# 5_-MCU_POWER.net
KiCad netlist of a schematic drawn in Altium Designer
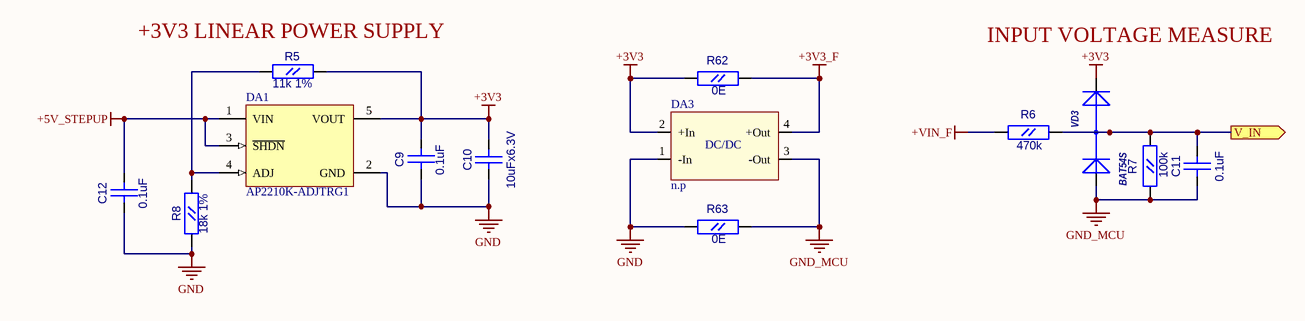
[diagram p0: [5]-MCU_POWER.SchDoc]

(export (version "E")
  (design (tool "Eeschema 10.0.6"))
  (components
    (comp (ref "C9")
      (value "0.1uF")
      (footprint "CC0603")
      (description "CC0603")
      (libsource (lib "gprs_modem_2") (part "CC0603"))
    )
    (comp (ref "C10")
      (value "10uFx6.3V")
      (footprint "CC0805")
      (description "CC0805")
      (libsource (lib "gprs_modem_2") (part "CC0805"))
    )
    (comp (ref "C11")
      (value "0.1uF")
      (footprint "CC0603")
      (description "CC0603")
      (libsource (lib "gprs_modem_2") (part "CC0603"))
    )
    (comp (ref "C12")
      (value "0.1uF")
      (footprint "CC0603")
      (description "CC0603")
      (libsource (lib "gprs_modem_2") (part "CC0603"))
    )
    (comp (ref "DA1")
      (value "AP2210K-ADJTRG1")
      (footprint "SOT23-5")
      (fields (field (name "PUBLISHER") "Altium Limited"))
      (libsource (lib "gprs_modem_2") (part "MCP1824T-ADJE/OT"))
    )
    (comp (ref "DA3")
      (value "n.p")
      (footprint "CME0303S3C")
      (description "DC/DC converter")
      (libsource (lib "fizik_lib") (part "CME0303S3C"))
    )
    (comp (ref "R5")
      (value "11k 1%")
      (footprint "RC0603")
      (description "RC0603")
      (libsource (lib "gprs_modem_2") (part "RC0603"))
    )
    (comp (ref "R6")
      (value "470k")
      (footprint "RC0603")
      (description "RC0603")
      (libsource (lib "fizik_lib") (part "RC0603"))
    )
    (comp (ref "R7")
      (value "100k")
      (footprint "RC0603")
      (description "RC0603")
      (libsource (lib "gprs_modem_2") (part "RC0603"))
    )
    (comp (ref "R8")
      (value "18k 1%")
      (footprint "RC0603")
      (description "RC0603")
      (libsource (lib "gprs_modem_2") (part "RC0603"))
    )
    (comp (ref "R62")
      (value "0E")
      (footprint "RC0805")
      (description "RC0805")
      (libsource (lib "fizik_lib") (part "RC0805"))
    )
    (comp (ref "R63")
      (value "0E")
      (footprint "RC0805")
      (description "RC0805")
      (libsource (lib "fizik_lib") (part "RC0805"))
    )
    (comp (ref "VD3")
      (value "BAT54S")
      (footprint "SOT-23(GSD)")
      (description "1.0 Ampere General Purpose Rectifier")
      (libsource (lib "gprs_modem_2") (part "BAT54S"))
    )
  )
  (nets
    (net (code "1") (name "+3V3") (class "Default")
      (node (ref "C10") (pin "2") (pinfunction "B_2") (pintype "passive"))
      (node (ref "C9") (pin "1") (pinfunction "A_1") (pintype "passive"))
      (node (ref "DA1") (pin "5") (pinfunction "VOUT_5") (pintype "power_in"))
      (node (ref "DA3") (pin "2") (pinfunction "+In_2") (pintype "passive"))
      (node (ref "R5") (pin "2") (pinfunction "B_2") (pintype "passive"))
      (node (ref "R62") (pin "1") (pinfunction "A_1") (pintype "passive"))
      (node (ref "VD3") (pin "2") (pinfunction "K_2") (pintype "passive"))
    )
    (net (code "2") (name "+3V3_F") (class "Default")
      (node (ref "DA3") (pin "4") (pinfunction "+Out_4") (pintype "passive"))
      (node (ref "R62") (pin "2") (pinfunction "B_2") (pintype "passive"))
    )
    (net (code "3") (name "+5V_STEPUP") (class "Default")
      (node (ref "C12") (pin "1") (pinfunction "A_1") (pintype "passive"))
      (node (ref "DA1") (pin "1") (pinfunction "VIN_1") (pintype "power_in"))
      (node (ref "DA1") (pin "3") (pinfunction "~{SHDN}_3") (pintype "input"))
    )
    (net (code "4") (name "+VIN_F") (class "Default")
      (node (ref "R6") (pin "1") (pinfunction "A_1") (pintype "passive"))
    )
    (net (code "5") (name "/V_IN") (class "Default")
      (node (ref "C11") (pin "2") (pinfunction "B_2") (pintype "passive"))
      (node (ref "R6") (pin "2") (pinfunction "B_2") (pintype "passive"))
      (node (ref "R7") (pin "2") (pinfunction "B_2") (pintype "passive"))
      (node (ref "VD3") (pin "3") (pinfunction "AK_3") (pintype "passive"))
    )
    (net (code "6") (name "GND") (class "Default")
      (node (ref "C10") (pin "1") (pinfunction "A_1") (pintype "passive"))
      (node (ref "C12") (pin "2") (pinfunction "B_2") (pintype "passive"))
      (node (ref "C9") (pin "2") (pinfunction "B_2") (pintype "passive"))
      (node (ref "DA1") (pin "2") (pinfunction "GND_2") (pintype "power_in"))
      (node (ref "DA3") (pin "1") (pinfunction "-In_1") (pintype "passive"))
      (node (ref "R63") (pin "1") (pinfunction "A_1") (pintype "passive"))
      (node (ref "R8") (pin "1") (pinfunction "A_1") (pintype "passive"))
    )
    (net (code "7") (name "GND_MCU") (class "Default")
      (node (ref "C11") (pin "1") (pinfunction "A_1") (pintype "passive"))
      (node (ref "DA3") (pin "3") (pinfunction "-Out_3") (pintype "passive"))
      (node (ref "R63") (pin "2") (pinfunction "B_2") (pintype "passive"))
      (node (ref "R7") (pin "1") (pinfunction "A_1") (pintype "passive"))
      (node (ref "VD3") (pin "1") (pinfunction "A_1") (pintype "passive"))
    )
    (net (code "8") (name "Net-(DA1-ADJ)") (class "Default")
      (node (ref "DA1") (pin "4") (pinfunction "ADJ_4") (pintype "input"))
      (node (ref "R5") (pin "1") (pinfunction "A_1") (pintype "passive"))
      (node (ref "R8") (pin "2") (pinfunction "B_2") (pintype "passive"))
    )
  )
)
